# Adafruit_NeoPixel_8_Stick_v2.net
KiCad netlist of a schematic drawn in EAGLE
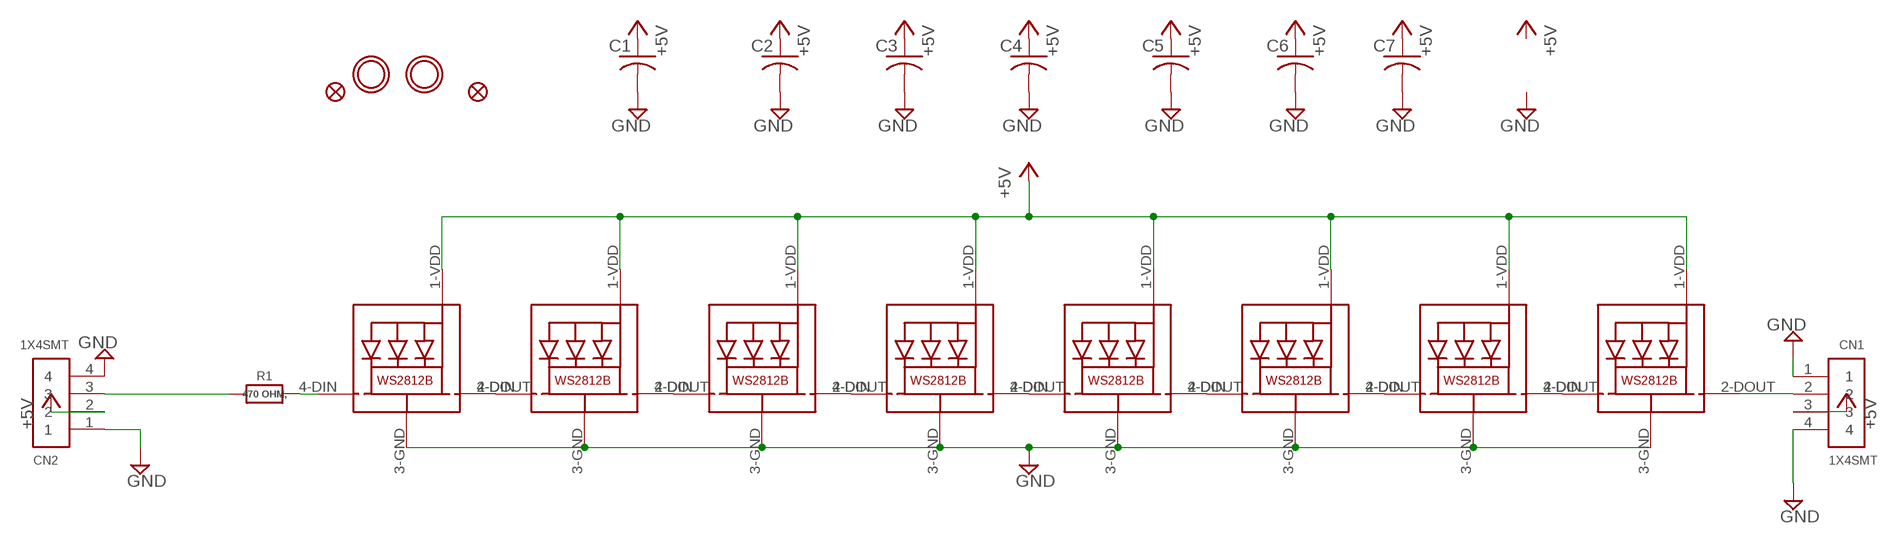
[diagram p0: schematic, sheet 1]

(export (version "E")
  (design (tool "Eeschema 10.0.6"))
  (components
    (comp (ref "C1")
      (value "C-USC0805K")
      (footprint "eagle-import:C0805K")
      (libsource (lib "eagle-import") (part "C-USC0805K"))
    )
    (comp (ref "C2")
      (value "C-USC0805K")
      (footprint "eagle-import:C0805K")
      (libsource (lib "eagle-import") (part "C-USC0805K"))
    )
    (comp (ref "C3")
      (value "C-USC0805K")
      (footprint "eagle-import:C0805K")
      (libsource (lib "eagle-import") (part "C-USC0805K"))
    )
    (comp (ref "C4")
      (value "C-USC0805K")
      (footprint "eagle-import:C0805K")
      (libsource (lib "eagle-import") (part "C-USC0805K"))
    )
    (comp (ref "C5")
      (value "C-USC0805K")
      (footprint "eagle-import:C0805K")
      (libsource (lib "eagle-import") (part "C-USC0805K"))
    )
    (comp (ref "C6")
      (value "C-USC0805K")
      (footprint "eagle-import:C0805K")
      (libsource (lib "eagle-import") (part "C-USC0805K"))
    )
    (comp (ref "C7")
      (value "C-USC0805K")
      (footprint "eagle-import:C0805K")
      (libsource (lib "eagle-import") (part "C-USC0805K"))
    )
    (comp (ref "CN1")
      (value "1X4SMT")
      (footprint "eagle-import:1X4-SMT")
      (libsource (lib "eagle-import") (part "1X4SMT"))
    )
    (comp (ref "CN2")
      (value "1X4SMT")
      (footprint "eagle-import:1X4-SMT")
      (libsource (lib "eagle-import") (part "1X4SMT"))
    )
    (comp (ref "FID1")
      (value "FIDUCIAL\"\"")
      (footprint "eagle-import:FIDUCIAL_1MM")
      (libsource (lib "eagle-import") (part "FIDUCIAL{dblquote}{dblquote}"))
    )
    (comp (ref "FID3")
      (value "FIDUCIAL\"\"")
      (footprint "eagle-import:FIDUCIAL_1MM")
      (libsource (lib "eagle-import") (part "FIDUCIAL{dblquote}{dblquote}"))
    )
    (comp (ref "LED1")
      (value "WS2812B5050-NARROW")
      (footprint "eagle-import:WS2812B-NARROW")
      (libsource (lib "eagle-import") (part "WS2812B5050-NARROW"))
    )
    (comp (ref "LED2")
      (value "WS2812B5050-NARROW")
      (footprint "eagle-import:WS2812B-NARROW")
      (libsource (lib "eagle-import") (part "WS2812B5050-NARROW"))
    )
    (comp (ref "LED3")
      (value "WS2812B5050-NARROW")
      (footprint "eagle-import:WS2812B-NARROW")
      (libsource (lib "eagle-import") (part "WS2812B5050-NARROW"))
    )
    (comp (ref "LED4")
      (value "WS2812B5050-NARROW")
      (footprint "eagle-import:WS2812B-NARROW")
      (libsource (lib "eagle-import") (part "WS2812B5050-NARROW"))
    )
    (comp (ref "LED5")
      (value "WS2812B5050-NARROW")
      (footprint "eagle-import:WS2812B-NARROW")
      (libsource (lib "eagle-import") (part "WS2812B5050-NARROW"))
    )
    (comp (ref "LED6")
      (value "WS2812B5050-NARROW")
      (footprint "eagle-import:WS2812B-NARROW")
      (libsource (lib "eagle-import") (part "WS2812B5050-NARROW"))
    )
    (comp (ref "LED7")
      (value "WS2812B5050-NARROW")
      (footprint "eagle-import:WS2812B-NARROW")
      (libsource (lib "eagle-import") (part "WS2812B5050-NARROW"))
    )
    (comp (ref "LED8")
      (value "WS2812B5050-NARROW")
      (footprint "eagle-import:WS2812B-NARROW")
      (libsource (lib "eagle-import") (part "WS2812B5050-NARROW"))
    )
    (comp (ref "R1")
      (value "470 OHM,")
      (footprint "eagle-import:_0805MP")
      (libsource (lib "eagle-import") (part "RESISTOR_0805MP"))
    )
    (comp (ref "U$2")
      (value "MOUNTINGHOLE2.0")
      (footprint "eagle-import:MOUNTINGHOLE_2.0_PLATED")
      (libsource (lib "eagle-import") (part "MOUNTINGHOLE2.0"))
    )
    (comp (ref "U$3")
      (value "MOUNTINGHOLE2.0")
      (footprint "eagle-import:MOUNTINGHOLE_2.0_PLATED")
      (libsource (lib "eagle-import") (part "MOUNTINGHOLE2.0"))
    )
  )
  (nets
    (net (code "1") (name "+5V") (class "Default")
      (node (ref "C1") (pin "1") (pinfunction "1_1") (pintype "passive"))
      (node (ref "C2") (pin "1") (pinfunction "1_1") (pintype "passive"))
      (node (ref "C3") (pin "1") (pinfunction "1_1") (pintype "passive"))
      (node (ref "C4") (pin "1") (pinfunction "1_1") (pintype "passive"))
      (node (ref "C5") (pin "1") (pinfunction "1_1") (pintype "passive"))
      (node (ref "C6") (pin "1") (pinfunction "1_1") (pintype "passive"))
      (node (ref "C7") (pin "1") (pinfunction "1_1") (pintype "passive"))
      (node (ref "CN1") (pin "3") (pinfunction "3_3") (pintype "bidirectional"))
      (node (ref "CN2") (pin "2") (pinfunction "2_2") (pintype "bidirectional"))
      (node (ref "LED1") (pin "1-VDD") (pinfunction "VDD_1-VDD") (pintype "power_in"))
      (node (ref "LED2") (pin "1-VDD") (pinfunction "VDD_1-VDD") (pintype "power_in"))
      (node (ref "LED3") (pin "1-VDD") (pinfunction "VDD_1-VDD") (pintype "power_in"))
      (node (ref "LED4") (pin "1-VDD") (pinfunction "VDD_1-VDD") (pintype "power_in"))
      (node (ref "LED5") (pin "1-VDD") (pinfunction "VDD_1-VDD") (pintype "power_in"))
      (node (ref "LED6") (pin "1-VDD") (pinfunction "VDD_1-VDD") (pintype "power_in"))
      (node (ref "LED7") (pin "1-VDD") (pinfunction "VDD_1-VDD") (pintype "power_in"))
      (node (ref "LED8") (pin "1-VDD") (pinfunction "VDD_1-VDD") (pintype "power_in"))
    )
    (net (code "2") (name "GND") (class "Default")
      (node (ref "C1") (pin "2") (pinfunction "2_2") (pintype "passive"))
      (node (ref "C2") (pin "2") (pinfunction "2_2") (pintype "passive"))
      (node (ref "C3") (pin "2") (pinfunction "2_2") (pintype "passive"))
      (node (ref "C4") (pin "2") (pinfunction "2_2") (pintype "passive"))
      (node (ref "C5") (pin "2") (pinfunction "2_2") (pintype "passive"))
      (node (ref "C6") (pin "2") (pinfunction "2_2") (pintype "passive"))
      (node (ref "C7") (pin "2") (pinfunction "2_2") (pintype "passive"))
      (node (ref "CN1") (pin "1") (pinfunction "1_1") (pintype "bidirectional"))
      (node (ref "CN1") (pin "4") (pinfunction "4_4") (pintype "bidirectional"))
      (node (ref "CN2") (pin "1") (pinfunction "1_1") (pintype "bidirectional"))
      (node (ref "CN2") (pin "4") (pinfunction "4_4") (pintype "bidirectional"))
      (node (ref "LED1") (pin "3-GND") (pinfunction "GND_3-GND") (pintype "power_in"))
      (node (ref "LED2") (pin "3-GND") (pinfunction "GND_3-GND") (pintype "power_in"))
      (node (ref "LED3") (pin "3-GND") (pinfunction "GND_3-GND") (pintype "power_in"))
      (node (ref "LED4") (pin "3-GND") (pinfunction "GND_3-GND") (pintype "power_in"))
      (node (ref "LED5") (pin "3-GND") (pinfunction "GND_3-GND") (pintype "power_in"))
      (node (ref "LED6") (pin "3-GND") (pinfunction "GND_3-GND") (pintype "power_in"))
      (node (ref "LED7") (pin "3-GND") (pinfunction "GND_3-GND") (pintype "power_in"))
      (node (ref "LED8") (pin "3-GND") (pinfunction "GND_3-GND") (pintype "power_in"))
    )
    (net (code "3") (name "Net-(CN2-Pad3)") (class "Default")
      (node (ref "CN2") (pin "3") (pinfunction "3_3") (pintype "bidirectional"))
      (node (ref "R1") (pin "1") (pinfunction "1_1") (pintype "passive"))
    )
    (net (code "4") (name "Net-(LED1-DI)") (class "Default")
      (node (ref "LED1") (pin "4-DIN") (pinfunction "DI_4-DIN") (pintype "input"))
      (node (ref "R1") (pin "2") (pinfunction "2_2") (pintype "passive"))
    )
    (net (code "5") (name "Net-(LED1-DO)") (class "Default")
      (node (ref "LED1") (pin "2-DOUT") (pinfunction "DO_2-DOUT") (pintype "output"))
      (node (ref "LED2") (pin "4-DIN") (pinfunction "DI_4-DIN") (pintype "input"))
    )
    (net (code "6") (name "Net-(LED2-DO)") (class "Default")
      (node (ref "LED2") (pin "2-DOUT") (pinfunction "DO_2-DOUT") (pintype "output"))
      (node (ref "LED3") (pin "4-DIN") (pinfunction "DI_4-DIN") (pintype "input"))
    )
    (net (code "7") (name "Net-(LED3-DO)") (class "Default")
      (node (ref "LED3") (pin "2-DOUT") (pinfunction "DO_2-DOUT") (pintype "output"))
      (node (ref "LED4") (pin "4-DIN") (pinfunction "DI_4-DIN") (pintype "input"))
    )
    (net (code "8") (name "Net-(LED4-DO)") (class "Default")
      (node (ref "LED4") (pin "2-DOUT") (pinfunction "DO_2-DOUT") (pintype "output"))
      (node (ref "LED5") (pin "4-DIN") (pinfunction "DI_4-DIN") (pintype "input"))
    )
    (net (code "9") (name "Net-(LED5-DO)") (class "Default")
      (node (ref "LED5") (pin "2-DOUT") (pinfunction "DO_2-DOUT") (pintype "output"))
      (node (ref "LED6") (pin "4-DIN") (pinfunction "DI_4-DIN") (pintype "input"))
    )
    (net (code "10") (name "Net-(LED6-DO)") (class "Default")
      (node (ref "LED6") (pin "2-DOUT") (pinfunction "DO_2-DOUT") (pintype "output"))
      (node (ref "LED7") (pin "4-DIN") (pinfunction "DI_4-DIN") (pintype "input"))
    )
    (net (code "11") (name "Net-(LED7-DO)") (class "Default")
      (node (ref "LED7") (pin "2-DOUT") (pinfunction "DO_2-DOUT") (pintype "output"))
      (node (ref "LED8") (pin "4-DIN") (pinfunction "DI_4-DIN") (pintype "input"))
    )
    (net (code "12") (name "Net-(LED8-DO)") (class "Default")
      (node (ref "CN1") (pin "2") (pinfunction "2_2") (pintype "bidirectional"))
      (node (ref "LED8") (pin "2-DOUT") (pinfunction "DO_2-DOUT") (pintype "output"))
    )
  )
)
